# daq_extention_board.net
KiCad netlist of a schematic drawn in EAGLE
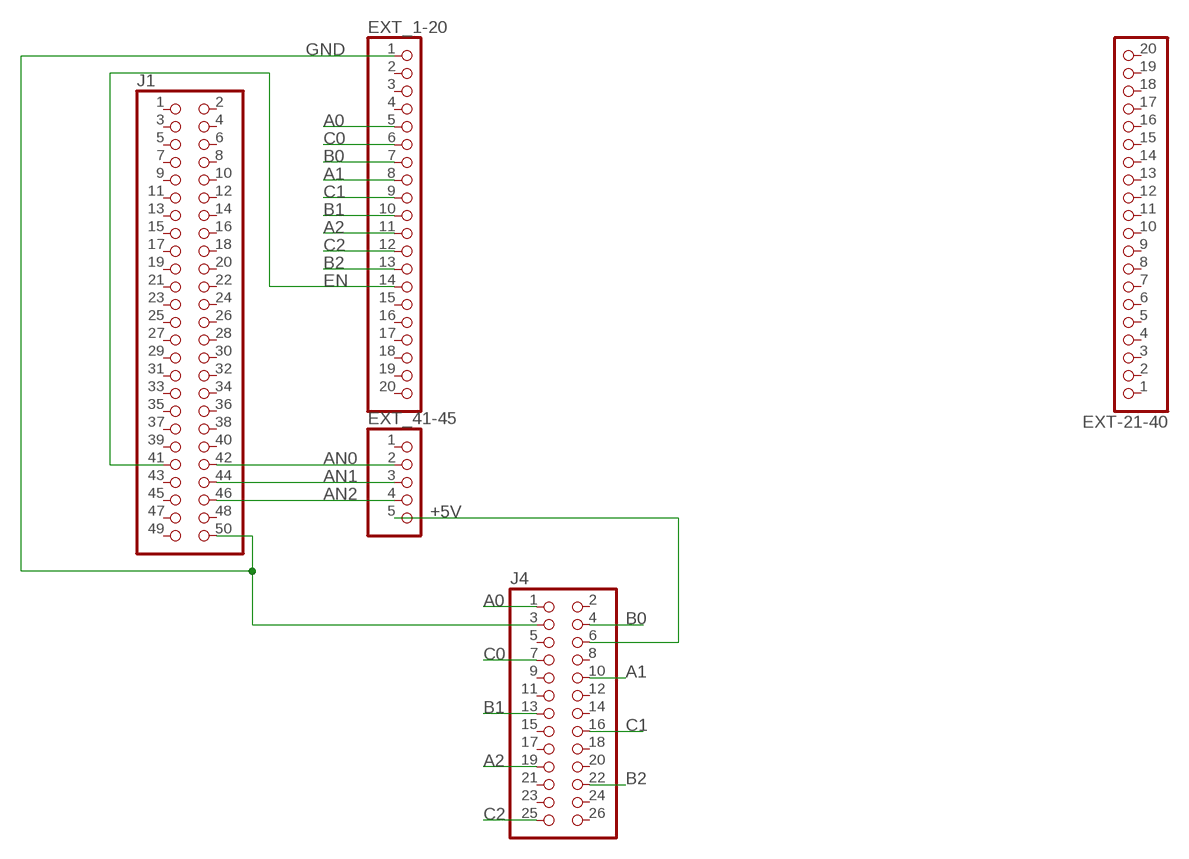
[diagram p0: schematic, sheet 1]

(export (version "E")
  (design (tool "Eeschema 10.0.6"))
  (components
    (comp (ref "EXT-21-40")
      (value "PINHD-1X20")
      (footprint "eagle-import:1X20")
      (libsource (lib "eagle-import") (part "PINHD-1X20"))
    )
    (comp (ref "EXT_1-20")
      (value "PINHD-1X20")
      (footprint "eagle-import:1X20")
      (libsource (lib "eagle-import") (part "PINHD-1X20"))
    )
    (comp (ref "EXT_41-45")
      (value "PINHD-1X5")
      (footprint "eagle-import:1X05")
      (libsource (lib "eagle-import") (part "PINHD-1X5"))
    )
    (comp (ref "J1")
      (value "PINHD-2X25")
      (footprint "eagle-import:2X25")
      (libsource (lib "eagle-import") (part "PINHD-2X25"))
    )
    (comp (ref "J4")
      (value "PINHD-2X13")
      (footprint "eagle-import:2X13")
      (libsource (lib "eagle-import") (part "PINHD-2X13"))
    )
  )
  (nets
    (net (code "1") (name "/+5V") (class "Default")
      (node (ref "EXT_41-45") (pin "5") (pinfunction "5_5") (pintype "passive"))
      (node (ref "J4") (pin "6") (pinfunction "6_6") (pintype "passive"))
    )
    (net (code "2") (name "/A0") (class "Default")
      (node (ref "EXT_1-20") (pin "5") (pinfunction "5_5") (pintype "passive"))
      (node (ref "J4") (pin "1") (pinfunction "1_1") (pintype "passive"))
    )
    (net (code "3") (name "/A1") (class "Default")
      (node (ref "EXT_1-20") (pin "8") (pinfunction "8_8") (pintype "passive"))
      (node (ref "J4") (pin "10") (pinfunction "10_10") (pintype "passive"))
    )
    (net (code "4") (name "/A2") (class "Default")
      (node (ref "EXT_1-20") (pin "11") (pinfunction "11_11") (pintype "passive"))
      (node (ref "J4") (pin "19") (pinfunction "19_19") (pintype "passive"))
    )
    (net (code "5") (name "/AN0") (class "Default")
      (node (ref "EXT_41-45") (pin "2") (pinfunction "2_2") (pintype "passive"))
      (node (ref "J1") (pin "42") (pinfunction "42_42") (pintype "passive"))
    )
    (net (code "6") (name "/AN1") (class "Default")
      (node (ref "EXT_41-45") (pin "3") (pinfunction "3_3") (pintype "passive"))
      (node (ref "J1") (pin "44") (pinfunction "44_44") (pintype "passive"))
    )
    (net (code "7") (name "/AN2") (class "Default")
      (node (ref "EXT_41-45") (pin "4") (pinfunction "4_4") (pintype "passive"))
      (node (ref "J1") (pin "46") (pinfunction "46_46") (pintype "passive"))
    )
    (net (code "8") (name "/B0") (class "Default")
      (node (ref "EXT_1-20") (pin "7") (pinfunction "7_7") (pintype "passive"))
      (node (ref "J4") (pin "4") (pinfunction "4_4") (pintype "passive"))
    )
    (net (code "9") (name "/B1") (class "Default")
      (node (ref "EXT_1-20") (pin "10") (pinfunction "10_10") (pintype "passive"))
      (node (ref "J4") (pin "13") (pinfunction "13_13") (pintype "passive"))
    )
    (net (code "10") (name "/B2") (class "Default")
      (node (ref "EXT_1-20") (pin "13") (pinfunction "13_13") (pintype "passive"))
      (node (ref "J4") (pin "22") (pinfunction "22_22") (pintype "passive"))
    )
    (net (code "11") (name "/C0") (class "Default")
      (node (ref "EXT_1-20") (pin "6") (pinfunction "6_6") (pintype "passive"))
      (node (ref "J4") (pin "7") (pinfunction "7_7") (pintype "passive"))
    )
    (net (code "12") (name "/C1") (class "Default")
      (node (ref "EXT_1-20") (pin "9") (pinfunction "9_9") (pintype "passive"))
      (node (ref "J4") (pin "16") (pinfunction "16_16") (pintype "passive"))
    )
    (net (code "13") (name "/C2") (class "Default")
      (node (ref "EXT_1-20") (pin "12") (pinfunction "12_12") (pintype "passive"))
      (node (ref "J4") (pin "25") (pinfunction "25_25") (pintype "passive"))
    )
    (net (code "14") (name "/EN") (class "Default")
      (node (ref "EXT_1-20") (pin "14") (pinfunction "14_14") (pintype "passive"))
      (node (ref "J1") (pin "41") (pinfunction "41_41") (pintype "passive"))
    )
    (net (code "15") (name "/GND") (class "Default")
      (node (ref "EXT_1-20") (pin "1") (pinfunction "1_1") (pintype "passive"))
      (node (ref "J1") (pin "50") (pinfunction "50_50") (pintype "passive"))
      (node (ref "J4") (pin "3") (pinfunction "3_3") (pintype "passive"))
    )
    (net (code "16") (name "unconnected-(EXT-21-40-Pad1)") (class "Default")
      (node (ref "EXT-21-40") (pin "1") (pinfunction "1_1") (pintype "passive"))
    )
    (net (code "17") (name "unconnected-(EXT-21-40-Pad2)") (class "Default")
      (node (ref "EXT-21-40") (pin "2") (pinfunction "2_2") (pintype "passive"))
    )
    (net (code "18") (name "unconnected-(EXT-21-40-Pad3)") (class "Default")
      (node (ref "EXT-21-40") (pin "3") (pinfunction "3_3") (pintype "passive"))
    )
    (net (code "19") (name "unconnected-(EXT-21-40-Pad4)") (class "Default")
      (node (ref "EXT-21-40") (pin "4") (pinfunction "4_4") (pintype "passive"))
    )
    (net (code "20") (name "unconnected-(EXT-21-40-Pad5)") (class "Default")
      (node (ref "EXT-21-40") (pin "5") (pinfunction "5_5") (pintype "passive"))
    )
    (net (code "21") (name "unconnected-(EXT-21-40-Pad6)") (class "Default")
      (node (ref "EXT-21-40") (pin "6") (pinfunction "6_6") (pintype "passive"))
    )
    (net (code "22") (name "unconnected-(EXT-21-40-Pad7)") (class "Default")
      (node (ref "EXT-21-40") (pin "7") (pinfunction "7_7") (pintype "passive"))
    )
    (net (code "23") (name "unconnected-(EXT-21-40-Pad8)") (class "Default")
      (node (ref "EXT-21-40") (pin "8") (pinfunction "8_8") (pintype "passive"))
    )
    (net (code "24") (name "unconnected-(EXT-21-40-Pad9)") (class "Default")
      (node (ref "EXT-21-40") (pin "9") (pinfunction "9_9") (pintype "passive"))
    )
    (net (code "25") (name "unconnected-(EXT-21-40-Pad10)") (class "Default")
      (node (ref "EXT-21-40") (pin "10") (pinfunction "10_10") (pintype "passive"))
    )
    (net (code "26") (name "unconnected-(EXT-21-40-Pad11)") (class "Default")
      (node (ref "EXT-21-40") (pin "11") (pinfunction "11_11") (pintype "passive"))
    )
    (net (code "27") (name "unconnected-(EXT-21-40-Pad12)") (class "Default")
      (node (ref "EXT-21-40") (pin "12") (pinfunction "12_12") (pintype "passive"))
    )
    (net (code "28") (name "unconnected-(EXT-21-40-Pad13)") (class "Default")
      (node (ref "EXT-21-40") (pin "13") (pinfunction "13_13") (pintype "passive"))
    )
    (net (code "29") (name "unconnected-(EXT-21-40-Pad14)") (class "Default")
      (node (ref "EXT-21-40") (pin "14") (pinfunction "14_14") (pintype "passive"))
    )
    (net (code "30") (name "unconnected-(EXT-21-40-Pad15)") (class "Default")
      (node (ref "EXT-21-40") (pin "15") (pinfunction "15_15") (pintype "passive"))
    )
    (net (code "31") (name "unconnected-(EXT-21-40-Pad16)") (class "Default")
      (node (ref "EXT-21-40") (pin "16") (pinfunction "16_16") (pintype "passive"))
    )
    (net (code "32") (name "unconnected-(EXT-21-40-Pad17)") (class "Default")
      (node (ref "EXT-21-40") (pin "17") (pinfunction "17_17") (pintype "passive"))
    )
    (net (code "33") (name "unconnected-(EXT-21-40-Pad18)") (class "Default")
      (node (ref "EXT-21-40") (pin "18") (pinfunction "18_18") (pintype "passive"))
    )
    (net (code "34") (name "unconnected-(EXT-21-40-Pad19)") (class "Default")
      (node (ref "EXT-21-40") (pin "19") (pinfunction "19_19") (pintype "passive"))
    )
    (net (code "35") (name "unconnected-(EXT-21-40-Pad20)") (class "Default")
      (node (ref "EXT-21-40") (pin "20") (pinfunction "20_20") (pintype "passive"))
    )
    (net (code "36") (name "unconnected-(EXT_1-20-Pad2)") (class "Default")
      (node (ref "EXT_1-20") (pin "2") (pinfunction "2_2") (pintype "passive"))
    )
    (net (code "37") (name "unconnected-(EXT_1-20-Pad3)") (class "Default")
      (node (ref "EXT_1-20") (pin "3") (pinfunction "3_3") (pintype "passive"))
    )
    (net (code "38") (name "unconnected-(EXT_1-20-Pad4)") (class "Default")
      (node (ref "EXT_1-20") (pin "4") (pinfunction "4_4") (pintype "passive"))
    )
    (net (code "39") (name "unconnected-(EXT_1-20-Pad15)") (class "Default")
      (node (ref "EXT_1-20") (pin "15") (pinfunction "15_15") (pintype "passive"))
    )
    (net (code "40") (name "unconnected-(EXT_1-20-Pad16)") (class "Default")
      (node (ref "EXT_1-20") (pin "16") (pinfunction "16_16") (pintype "passive"))
    )
    (net (code "41") (name "unconnected-(EXT_1-20-Pad17)") (class "Default")
      (node (ref "EXT_1-20") (pin "17") (pinfunction "17_17") (pintype "passive"))
    )
    (net (code "42") (name "unconnected-(EXT_1-20-Pad18)") (class "Default")
      (node (ref "EXT_1-20") (pin "18") (pinfunction "18_18") (pintype "passive"))
    )
    (net (code "43") (name "unconnected-(EXT_1-20-Pad19)") (class "Default")
      (node (ref "EXT_1-20") (pin "19") (pinfunction "19_19") (pintype "passive"))
    )
    (net (code "44") (name "unconnected-(EXT_1-20-Pad20)") (class "Default")
      (node (ref "EXT_1-20") (pin "20") (pinfunction "20_20") (pintype "passive"))
    )
    (net (code "45") (name "unconnected-(EXT_41-45-Pad1)") (class "Default")
      (node (ref "EXT_41-45") (pin "1") (pinfunction "1_1") (pintype "passive"))
    )
    (net (code "46") (name "unconnected-(J1-Pad1)") (class "Default")
      (node (ref "J1") (pin "1") (pinfunction "1_1") (pintype "passive"))
    )
    (net (code "47") (name "unconnected-(J1-Pad2)") (class "Default")
      (node (ref "J1") (pin "2") (pinfunction "2_2") (pintype "passive"))
    )
    (net (code "48") (name "unconnected-(J1-Pad3)") (class "Default")
      (node (ref "J1") (pin "3") (pinfunction "3_3") (pintype "passive"))
    )
    (net (code "49") (name "unconnected-(J1-Pad4)") (class "Default")
      (node (ref "J1") (pin "4") (pinfunction "4_4") (pintype "passive"))
    )
    (net (code "50") (name "unconnected-(J1-Pad5)") (class "Default")
      (node (ref "J1") (pin "5") (pinfunction "5_5") (pintype "passive"))
    )
    (net (code "51") (name "unconnected-(J1-Pad6)") (class "Default")
      (node (ref "J1") (pin "6") (pinfunction "6_6") (pintype "passive"))
    )
    (net (code "52") (name "unconnected-(J1-Pad7)") (class "Default")
      (node (ref "J1") (pin "7") (pinfunction "7_7") (pintype "passive"))
    )
    (net (code "53") (name "unconnected-(J1-Pad8)") (class "Default")
      (node (ref "J1") (pin "8") (pinfunction "8_8") (pintype "passive"))
    )
    (net (code "54") (name "unconnected-(J1-Pad9)") (class "Default")
      (node (ref "J1") (pin "9") (pinfunction "9_9") (pintype "passive"))
    )
    (net (code "55") (name "unconnected-(J1-Pad10)") (class "Default")
      (node (ref "J1") (pin "10") (pinfunction "10_10") (pintype "passive"))
    )
    (net (code "56") (name "unconnected-(J1-Pad11)") (class "Default")
      (node (ref "J1") (pin "11") (pinfunction "11_11") (pintype "passive"))
    )
    (net (code "57") (name "unconnected-(J1-Pad12)") (class "Default")
      (node (ref "J1") (pin "12") (pinfunction "12_12") (pintype "passive"))
    )
    (net (code "58") (name "unconnected-(J1-Pad13)") (class "Default")
      (node (ref "J1") (pin "13") (pinfunction "13_13") (pintype "passive"))
    )
    (net (code "59") (name "unconnected-(J1-Pad14)") (class "Default")
      (node (ref "J1") (pin "14") (pinfunction "14_14") (pintype "passive"))
    )
    (net (code "60") (name "unconnected-(J1-Pad15)") (class "Default")
      (node (ref "J1") (pin "15") (pinfunction "15_15") (pintype "passive"))
    )
    (net (code "61") (name "unconnected-(J1-Pad16)") (class "Default")
      (node (ref "J1") (pin "16") (pinfunction "16_16") (pintype "passive"))
    )
    (net (code "62") (name "unconnected-(J1-Pad17)") (class "Default")
      (node (ref "J1") (pin "17") (pinfunction "17_17") (pintype "passive"))
    )
    (net (code "63") (name "unconnected-(J1-Pad18)") (class "Default")
      (node (ref "J1") (pin "18") (pinfunction "18_18") (pintype "passive"))
    )
    (net (code "64") (name "unconnected-(J1-Pad19)") (class "Default")
      (node (ref "J1") (pin "19") (pinfunction "19_19") (pintype "passive"))
    )
    (net (code "65") (name "unconnected-(J1-Pad20)") (class "Default")
      (node (ref "J1") (pin "20") (pinfunction "20_20") (pintype "passive"))
    )
    (net (code "66") (name "unconnected-(J1-Pad21)") (class "Default")
      (node (ref "J1") (pin "21") (pinfunction "21_21") (pintype "passive"))
    )
    (net (code "67") (name "unconnected-(J1-Pad22)") (class "Default")
      (node (ref "J1") (pin "22") (pinfunction "22_22") (pintype "passive"))
    )
    (net (code "68") (name "unconnected-(J1-Pad23)") (class "Default")
      (node (ref "J1") (pin "23") (pinfunction "23_23") (pintype "passive"))
    )
    (net (code "69") (name "unconnected-(J1-Pad24)") (class "Default")
      (node (ref "J1") (pin "24") (pinfunction "24_24") (pintype "passive"))
    )
    (net (code "70") (name "unconnected-(J1-Pad25)") (class "Default")
      (node (ref "J1") (pin "25") (pinfunction "25_25") (pintype "passive"))
    )
    (net (code "71") (name "unconnected-(J1-Pad26)") (class "Default")
      (node (ref "J1") (pin "26") (pinfunction "26_26") (pintype "passive"))
    )
    (net (code "72") (name "unconnected-(J1-Pad27)") (class "Default")
      (node (ref "J1") (pin "27") (pinfunction "27_27") (pintype "passive"))
    )
    (net (code "73") (name "unconnected-(J1-Pad28)") (class "Default")
      (node (ref "J1") (pin "28") (pinfunction "28_28") (pintype "passive"))
    )
    (net (code "74") (name "unconnected-(J1-Pad29)") (class "Default")
      (node (ref "J1") (pin "29") (pinfunction "29_29") (pintype "passive"))
    )
    (net (code "75") (name "unconnected-(J1-Pad30)") (class "Default")
      (node (ref "J1") (pin "30") (pinfunction "30_30") (pintype "passive"))
    )
    (net (code "76") (name "unconnected-(J1-Pad31)") (class "Default")
      (node (ref "J1") (pin "31") (pinfunction "31_31") (pintype "passive"))
    )
    (net (code "77") (name "unconnected-(J1-Pad32)") (class "Default")
      (node (ref "J1") (pin "32") (pinfunction "32_32") (pintype "passive"))
    )
    (net (code "78") (name "unconnected-(J1-Pad33)") (class "Default")
      (node (ref "J1") (pin "33") (pinfunction "33_33") (pintype "passive"))
    )
    (net (code "79") (name "unconnected-(J1-Pad34)") (class "Default")
      (node (ref "J1") (pin "34") (pinfunction "34_34") (pintype "passive"))
    )
    (net (code "80") (name "unconnected-(J1-Pad35)") (class "Default")
      (node (ref "J1") (pin "35") (pinfunction "35_35") (pintype "passive"))
    )
    (net (code "81") (name "unconnected-(J1-Pad36)") (class "Default")
      (node (ref "J1") (pin "36") (pinfunction "36_36") (pintype "passive"))
    )
    (net (code "82") (name "unconnected-(J1-Pad37)") (class "Default")
      (node (ref "J1") (pin "37") (pinfunction "37_37") (pintype "passive"))
    )
    (net (code "83") (name "unconnected-(J1-Pad38)") (class "Default")
      (node (ref "J1") (pin "38") (pinfunction "38_38") (pintype "passive"))
    )
    (net (code "84") (name "unconnected-(J1-Pad39)") (class "Default")
      (node (ref "J1") (pin "39") (pinfunction "39_39") (pintype "passive"))
    )
    (net (code "85") (name "unconnected-(J1-Pad40)") (class "Default")
      (node (ref "J1") (pin "40") (pinfunction "40_40") (pintype "passive"))
    )
    (net (code "86") (name "unconnected-(J1-Pad43)") (class "Default")
      (node (ref "J1") (pin "43") (pinfunction "43_43") (pintype "passive"))
    )
    (net (code "87") (name "unconnected-(J1-Pad45)") (class "Default")
      (node (ref "J1") (pin "45") (pinfunction "45_45") (pintype "passive"))
    )
    (net (code "88") (name "unconnected-(J1-Pad47)") (class "Default")
      (node (ref "J1") (pin "47") (pinfunction "47_47") (pintype "passive"))
    )
    (net (code "89") (name "unconnected-(J1-Pad48)") (class "Default")
      (node (ref "J1") (pin "48") (pinfunction "48_48") (pintype "passive"))
    )
    (net (code "90") (name "unconnected-(J1-Pad49)") (class "Default")
      (node (ref "J1") (pin "49") (pinfunction "49_49") (pintype "passive"))
    )
    (net (code "91") (name "unconnected-(J4-Pad2)") (class "Default")
      (node (ref "J4") (pin "2") (pinfunction "2_2") (pintype "passive"))
    )
    (net (code "92") (name "unconnected-(J4-Pad5)") (class "Default")
      (node (ref "J4") (pin "5") (pinfunction "5_5") (pintype "passive"))
    )
    (net (code "93") (name "unconnected-(J4-Pad8)") (class "Default")
      (node (ref "J4") (pin "8") (pinfunction "8_8") (pintype "passive"))
    )
    (net (code "94") (name "unconnected-(J4-Pad9)") (class "Default")
      (node (ref "J4") (pin "9") (pinfunction "9_9") (pintype "passive"))
    )
    (net (code "95") (name "unconnected-(J4-Pad11)") (class "Default")
      (node (ref "J4") (pin "11") (pinfunction "11_11") (pintype "passive"))
    )
    (net (code "96") (name "unconnected-(J4-Pad12)") (class "Default")
      (node (ref "J4") (pin "12") (pinfunction "12_12") (pintype "passive"))
    )
    (net (code "97") (name "unconnected-(J4-Pad14)") (class "Default")
      (node (ref "J4") (pin "14") (pinfunction "14_14") (pintype "passive"))
    )
    (net (code "98") (name "unconnected-(J4-Pad15)") (class "Default")
      (node (ref "J4") (pin "15") (pinfunction "15_15") (pintype "passive"))
    )
    (net (code "99") (name "unconnected-(J4-Pad17)") (class "Default")
      (node (ref "J4") (pin "17") (pinfunction "17_17") (pintype "passive"))
    )
    (net (code "100") (name "unconnected-(J4-Pad18)") (class "Default")
      (node (ref "J4") (pin "18") (pinfunction "18_18") (pintype "passive"))
    )
    (net (code "101") (name "unconnected-(J4-Pad20)") (class "Default")
      (node (ref "J4") (pin "20") (pinfunction "20_20") (pintype "passive"))
    )
    (net (code "102") (name "unconnected-(J4-Pad21)") (class "Default")
      (node (ref "J4") (pin "21") (pinfunction "21_21") (pintype "passive"))
    )
    (net (code "103") (name "unconnected-(J4-Pad23)") (class "Default")
      (node (ref "J4") (pin "23") (pinfunction "23_23") (pintype "passive"))
    )
    (net (code "104") (name "unconnected-(J4-Pad24)") (class "Default")
      (node (ref "J4") (pin "24") (pinfunction "24_24") (pintype "passive"))
    )
    (net (code "105") (name "unconnected-(J4-Pad26)") (class "Default")
      (node (ref "J4") (pin "26") (pinfunction "26_26") (pintype "passive"))
    )
  )
)
